# power.net
KiCad netlist of a schematic drawn in Altium Designer
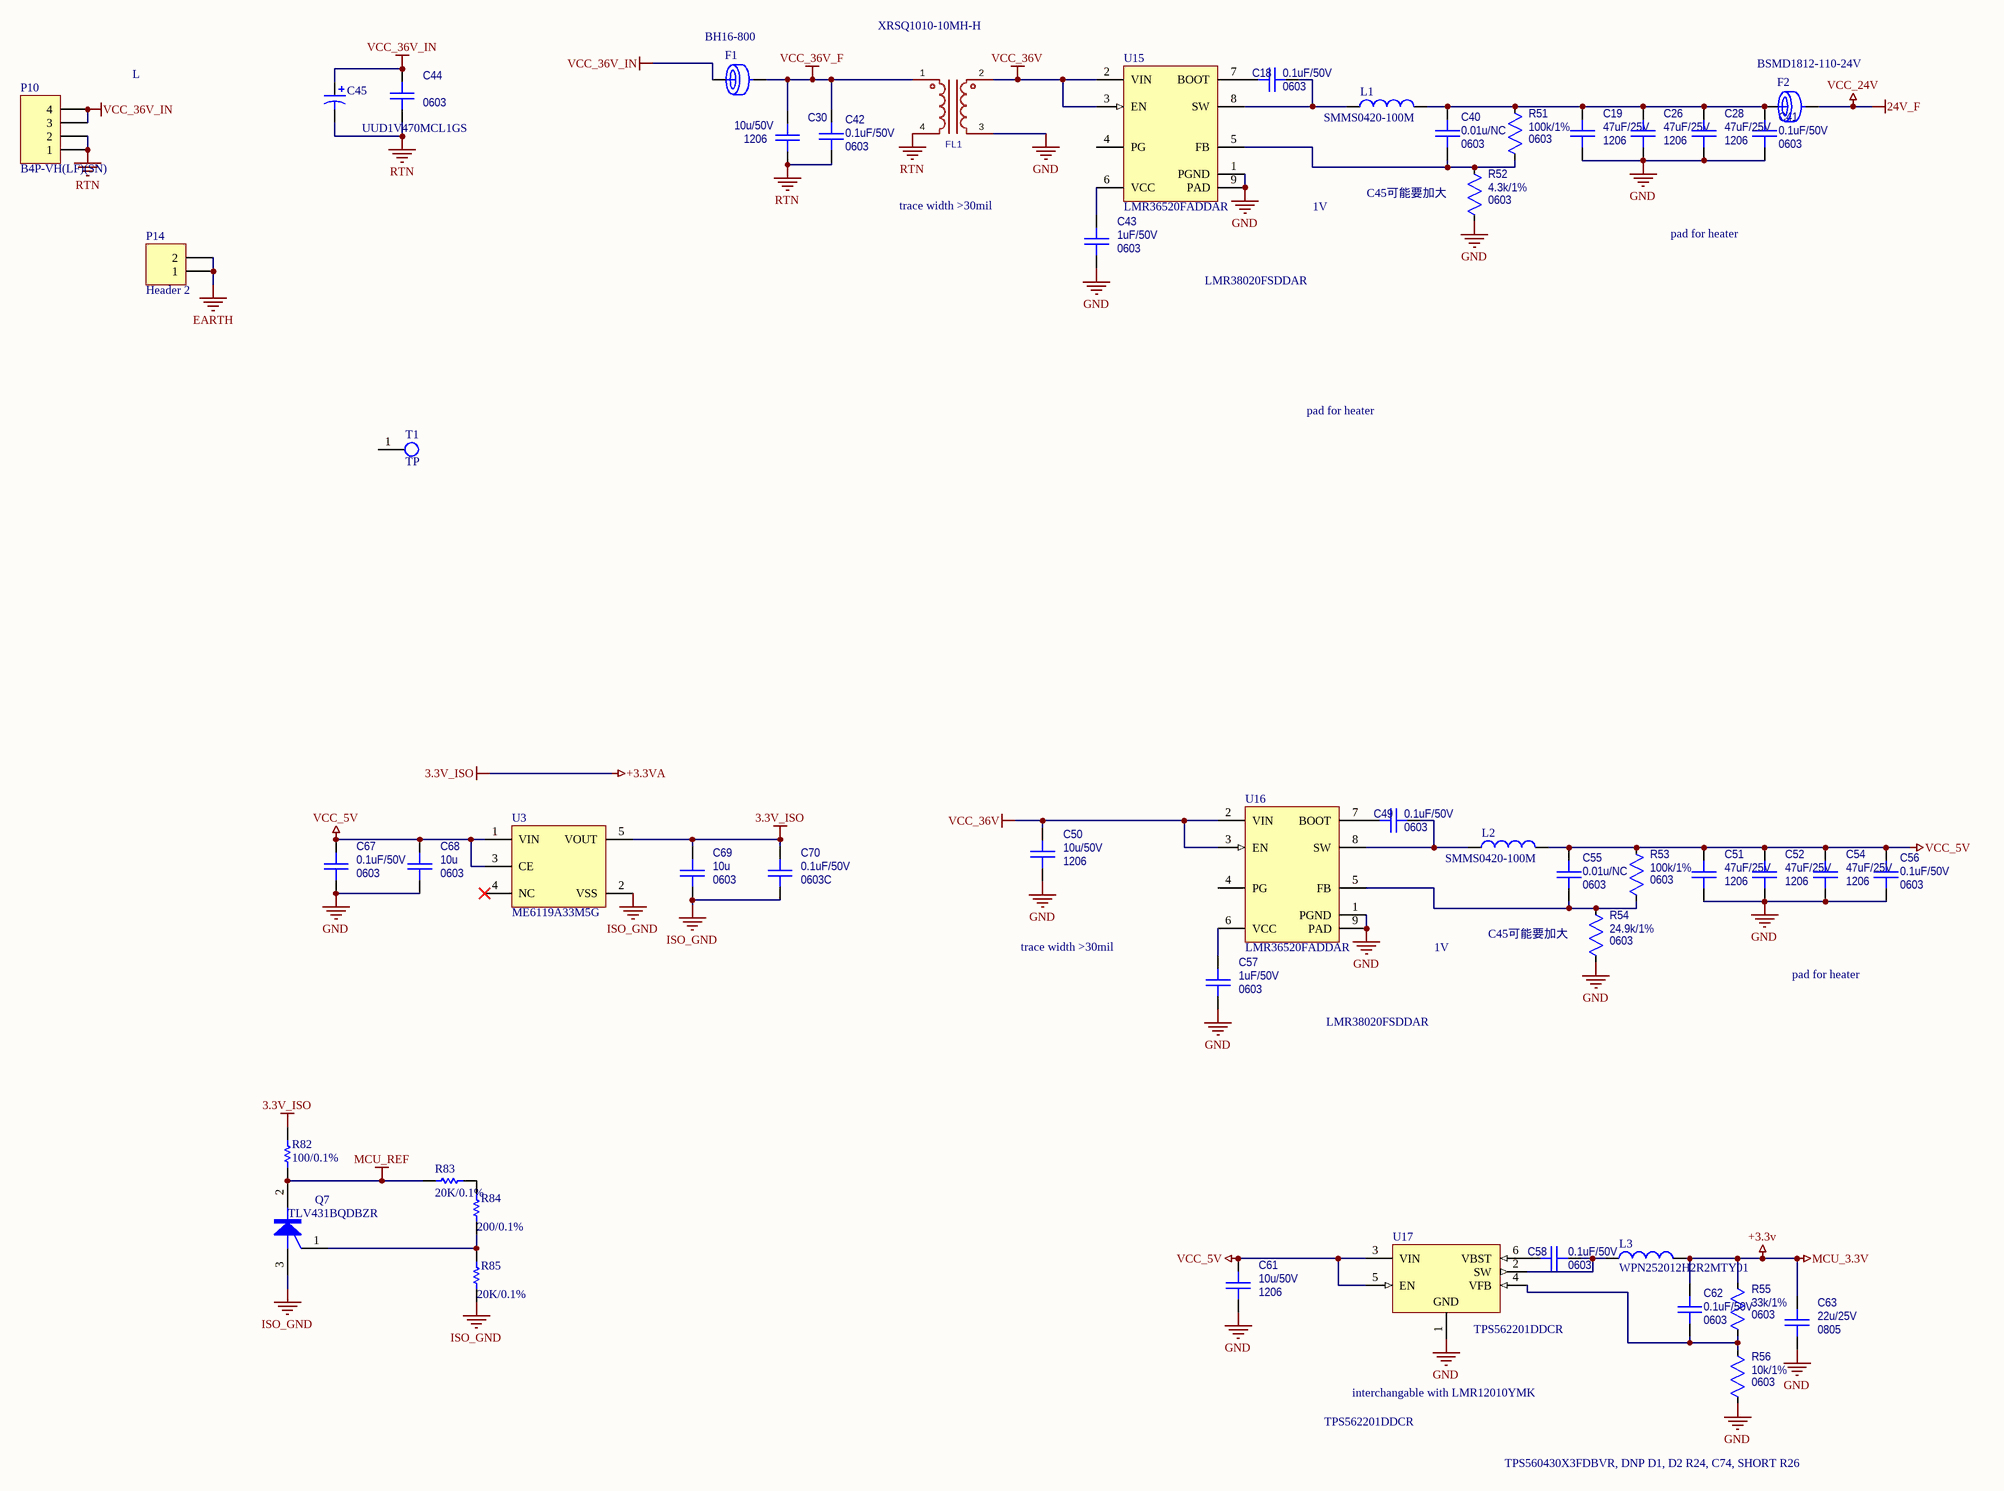
[diagram p0: power.SchDoc]

(export (version "E")
  (design (tool "Eeschema 10.0.6"))
  (components
    (comp (ref "C18")
      (value "0.1uF/50V")
      (footprint "0603C")
      (fields (field (name "PACKAGE") "0603"))
      (libsource (lib "Karl") (part "Capacitor_0603"))
    )
    (comp (ref "C19")
      (value "47uF/25V")
      (footprint "CAPC3216X156N_1206")
      (fields (field (name "PACKAGE") "1206"))
      (libsource (lib "Karl") (part "Capacitor_1206"))
    )
    (comp (ref "C26")
      (value "47uF/25V")
      (footprint "CAPC3216X156N_1206")
      (fields (field (name "PACKAGE") "1206"))
      (libsource (lib "Karl") (part "Capacitor_1206"))
    )
    (comp (ref "C28")
      (value "47uF/25V")
      (footprint "CAPC3216X156N_1206")
      (fields (field (name "PACKAGE") "1206"))
      (libsource (lib "Karl") (part "Capacitor_1206"))
    )
    (comp (ref "C30")
      (value "10u/50V")
      (footprint "CAPC3216X156N_1206")
      (fields (field (name "PACKAGE") "1206"))
      (libsource (lib "Karl") (part "Capacitor_1206"))
    )
    (comp (ref "C40")
      (value "0.01u/NC")
      (footprint "0603C")
      (fields (field (name "PACKAGE") "0603") (field (name "Comment") "0.01uF/50V"))
      (libsource (lib "Karl") (part "Capacitor_0603"))
    )
    (comp (ref "C41")
      (value "0.1uF/50V")
      (footprint "0603C")
      (fields (field (name "PACKAGE") "0603"))
      (libsource (lib "Karl") (part "Capacitor_0603"))
    )
    (comp (ref "C42")
      (value "0.1uF/50V")
      (footprint "0603C")
      (fields (field (name "PACKAGE") "0603"))
      (libsource (lib "Karl") (part "Capacitor_0603"))
    )
    (comp (ref "C43")
      (value "1uF/50V")
      (footprint "0603C")
      (fields (field (name "PACKAGE") "0603"))
      (libsource (lib "Karl") (part "Capacitor_0603"))
    )
    (comp (ref "C44")
      (value "10uF/16V")
      (footprint "0603c")
      (description "Capacitor, MLCC")
      (fields (field (name "PACKAGE") "0603"))
      (libsource (lib "Karl") (part "Capacitor_0603"))
    )
    (comp (ref "C45")
      (value "UUD1V470MCL1GS")
      (footprint "Φ10×10")
      (description "Polarized Capacitor (Radial)")
      (libsource (lib "Miscellaneous Devices") (part "Cap Pol1"))
    )
    (comp (ref "C49")
      (value "0.1uF/50V")
      (footprint "0603C")
      (fields (field (name "PACKAGE") "0603"))
      (libsource (lib "Karl") (part "Capacitor_0603"))
    )
    (comp (ref "C50")
      (value "10u/50V")
      (footprint "CAPC3216X156N_1206")
      (fields (field (name "PACKAGE") "1206"))
      (libsource (lib "Karl") (part "Capacitor_1206"))
    )
    (comp (ref "C51")
      (value "47uF/25V")
      (footprint "CAPC3216X156N_1206")
      (fields (field (name "PACKAGE") "1206"))
      (libsource (lib "Karl") (part "Capacitor_1206"))
    )
    (comp (ref "C52")
      (value "47uF/25V")
      (footprint "CAPC3216X156N_1206")
      (fields (field (name "PACKAGE") "1206"))
      (libsource (lib "Karl") (part "Capacitor_1206"))
    )
    (comp (ref "C54")
      (value "47uF/25V")
      (footprint "CAPC3216X156N_1206")
      (fields (field (name "PACKAGE") "1206"))
      (libsource (lib "Karl") (part "Capacitor_1206"))
    )
    (comp (ref "C55")
      (value "0.01u/NC")
      (footprint "0603C")
      (fields (field (name "PACKAGE") "0603") (field (name "Comment") "0.01uF/50V"))
      (libsource (lib "Karl") (part "Capacitor_0603"))
    )
    (comp (ref "C56")
      (value "0.1uF/50V")
      (footprint "0603C")
      (fields (field (name "PACKAGE") "0603"))
      (libsource (lib "Karl") (part "Capacitor_0603"))
    )
    (comp (ref "C57")
      (value "1uF/50V")
      (footprint "0603C")
      (fields (field (name "PACKAGE") "0603"))
      (libsource (lib "Karl") (part "Capacitor_0603"))
    )
    (comp (ref "C58")
      (value "0.1uF/50V")
      (footprint "0603C")
      (fields (field (name "PACKAGE") "0603"))
      (libsource (lib "Karl") (part "Capacitor_0603"))
    )
    (comp (ref "C61")
      (value "10u/50V")
      (footprint "CAPC3216X156N_1206")
      (fields (field (name "PACKAGE") "1206"))
      (libsource (lib "Karl") (part "Capacitor_0805"))
    )
    (comp (ref "C62")
      (value "0.1uF/50V")
      (footprint "0603C")
      (fields (field (name "PACKAGE") "0603"))
      (libsource (lib "Karl") (part "Capacitor_0603"))
    )
    (comp (ref "C63")
      (value "22u/25V")
      (footprint "CAPC2012X127N_0805")
      (fields (field (name "PACKAGE") "0805"))
      (libsource (lib "Karl") (part "Capacitor_0805"))
    )
    (comp (ref "C67")
      (value "0.1uF/50V")
      (footprint "0603C")
      (description "Capacitor, MLCC")
      (fields (field (name "PACKAGE") "0603"))
      (libsource (lib "Karl") (part "Capacitor_0603"))
    )
    (comp (ref "C68")
      (value "10u")
      (footprint "0603c")
      (description "Capacitor, MLCC")
      (fields (field (name "PACKAGE") "0603") (field (name "Comment") "10uF/16V"))
      (libsource (lib "Karl") (part "Capacitor_0603"))
    )
    (comp (ref "C69")
      (value "10u")
      (footprint "0603c")
      (description "Capacitor, MLCC")
      (fields (field (name "PACKAGE") "0603") (field (name "Comment") "10uF/16V"))
      (libsource (lib "Karl") (part "Capacitor_0603"))
    )
    (comp (ref "C70")
      (value "0.1uF/50V")
      (footprint "0603C")
      (description "Capacitor, MLCC")
      (fields (field (name "PACKAGE") "0603C"))
      (libsource (lib "Karl") (part "Capacitor_0402"))
    )
    (comp (ref "F1")
      (value "BH16-800")
      (footprint "FUSE-TH_L14.0-W3.0-P5.10-D0.8-LS1.20")
      (description "Ferrite Bead Chip")
      (libsource (lib "Karl") (part "FBC0603"))
    )
    (comp (ref "F2")
      (value "BSMD1812-110-24V")
      (footprint "1812-F")
      (description "Ferrite Bead Chip")
      (libsource (lib "Karl") (part "FBC0603"))
    )
    (comp (ref "FL1")
      (value "XRSQ1010-10MH-H")
      (footprint "IND-TH_4P-L14.0-W12.0_XRSQ1010-10MH-H")
      (libsource (lib "altium-import") (part "root_0_XRSQ1010-10MH-H_"))
    )
    (comp (ref "L1")
      (value "SMMS0420-100M")
      (footprint "IND-SMD_L4.5-W4.5_SMMS0420:IND-SMD_L4.5-W4.5_SMMS0420")
      (description "Metal alloy Power Inductor, 10 uH, ±20%, 1210 (3225)")
      (libsource (lib "Bogen") (part "1276AS-H-100M=P2"))
    )
    (comp (ref "L2")
      (value "SMMS0420-100M")
      (footprint "IND-SMD_L4.5-W4.5_SMMS0420:IND-SMD_L4.5-W4.5_SMMS0420")
      (description "Metal alloy Power Inductor, 10 uH, ±20%, 1210 (3225)")
      (libsource (lib "Bogen") (part "1276AS-H-100M=P2"))
    )
    (comp (ref "L3")
      (value "WPN252012H2R2MTY01")
      (footprint "PULS-BDCD00252012_V")
      (libsource (lib "Bogen") (part "BDCD002520122R2MS1"))
    )
    (comp (ref "P10")
      (value "B4P-VH(LF)(SN)")
      (footprint "CONN-TH_4P-P3.96_HX-VH3.96-4P-ZZ")
      (description "Header, 4-Pin")
      (libsource (lib "Miscellaneous Connectors") (part "Header 4"))
    )
    (comp (ref "P14")
      (value "Header 2")
      (footprint "插片端子4.8*0.8mm")
      (description "Header, 2-Pin")
      (libsource (lib "Miscellaneous Connectors") (part "Header 2"))
    )
    (comp (ref "Q7")
      (value "TLV431BQDBZR")
      (footprint "SOT23-3")
      (description "Programmable Unijunction Transistor")
      (libsource (lib "Miscellaneous Devices") (part "PUT"))
    )
    (comp (ref "R51")
      (value "100k/1%")
      (footprint "0603R")
      (fields (field (name "PACKAGE") "0603"))
      (libsource (lib "Karl") (part "Resistor_0603"))
    )
    (comp (ref "R52")
      (value "4.3k/1%")
      (footprint "0603R")
      (fields (field (name "PACKAGE") "0603"))
      (libsource (lib "Karl") (part "Resistor_0603"))
    )
    (comp (ref "R53")
      (value "100k/1%")
      (footprint "0603R")
      (fields (field (name "PACKAGE") "0603"))
      (libsource (lib "Karl") (part "Resistor_0603"))
    )
    (comp (ref "R54")
      (value "24.9k/1%")
      (footprint "0603R")
      (fields (field (name "PACKAGE") "0603"))
      (libsource (lib "Karl") (part "Resistor_0603"))
    )
    (comp (ref "R55")
      (value "33k/1%")
      (footprint "0603R")
      (fields (field (name "PACKAGE") "0603"))
      (libsource (lib "Karl") (part "Resistor_0603"))
    )
    (comp (ref "R56")
      (value "10k/1%")
      (footprint "0603R")
      (fields (field (name "PACKAGE") "0603"))
      (libsource (lib "Karl") (part "Resistor_0603"))
    )
    (comp (ref "R82")
      (value "100/0.1%")
      (footprint "0603R")
      (description "Resistor")
      (libsource (lib "Miscellaneous Devices") (part "Res1"))
    )
    (comp (ref "R83")
      (value "20K/0.1%")
      (footprint "0603R")
      (description "Resistor")
      (libsource (lib "Miscellaneous Devices") (part "Res1"))
    )
    (comp (ref "R84")
      (value "200/0.1%")
      (footprint "0603R")
      (description "Resistor")
      (libsource (lib "Miscellaneous Devices") (part "Res1"))
    )
    (comp (ref "R85")
      (value "20K/0.1%")
      (footprint "0603R")
      (description "Resistor")
      (libsource (lib "Miscellaneous Devices") (part "Res1"))
    )
    (comp (ref "T1") (value "TP") (footprint "SQP-1181C") (libsource (lib "Schlib_20110825") (part "TP")))
    (comp (ref "U3")
      (value "ME6119A33M5G")
      (footprint "MCRN-SOT23-5_V")
      (libsource (lib "Bogen") (part "ME6119C50M5G"))
    )
    (comp (ref "U15")
      (value "LMR36520FADDAR")
      (footprint "DDA0008A_M")
      (libsource (lib "Bogen") (part "LMR36520FADDAR"))
    )
    (comp (ref "U16")
      (value "LMR36520FADDAR")
      (footprint "DDA0008A_M")
      (libsource (lib "Bogen") (part "LMR36520FADDAR"))
    )
    (comp (ref "U17")
      (value "TPS562201DDCR")
      (footprint "DDC0006A_L")
      (libsource (lib "Bogen") (part "TPS562201DDCR"))
    )
  )
  (nets
    (net (code "1") (name "+3.3VA") (class "Default")
      (node (ref "C69") (pin "1") (pinfunction "1_1") (pintype "passive"))
      (node (ref "C70") (pin "1") (pinfunction "1_1") (pintype "passive"))
      (node (ref "R82") (pin "1") (pinfunction "1_1") (pintype "passive"))
      (node (ref "U3") (pin "5") (pinfunction "VOUT_5") (pintype "passive"))
    )
    (net (code "2") (name "+3.3v") (class "Default")
      (node (ref "C62") (pin "1") (pinfunction "1_1") (pintype "passive"))
      (node (ref "C63") (pin "1") (pinfunction "1_1") (pintype "passive"))
      (node (ref "L3") (pin "2") (pinfunction "2_2") (pintype "passive"))
      (node (ref "R55") (pin "2") (pinfunction "2_2") (pintype "passive"))
    )
    (net (code "3") (name "24V_F") (class "Default")
      (node (ref "F2") (pin "2") (pinfunction "2_2") (pintype "passive"))
    )
    (net (code "4") (name "EARTH") (class "Default")
      (node (ref "P14") (pin "1") (pinfunction "1_1") (pintype "passive"))
      (node (ref "P14") (pin "2") (pinfunction "2_2") (pintype "passive"))
    )
    (net (code "5") (name "GND") (class "Default")
      (node (ref "C19") (pin "2") (pinfunction "2_2") (pintype "passive"))
      (node (ref "C26") (pin "2") (pinfunction "2_2") (pintype "passive"))
      (node (ref "C28") (pin "2") (pinfunction "2_2") (pintype "passive"))
      (node (ref "C41") (pin "2") (pinfunction "2_2") (pintype "passive"))
      (node (ref "C43") (pin "2") (pinfunction "2_2") (pintype "passive"))
      (node (ref "C50") (pin "2") (pinfunction "2_2") (pintype "passive"))
      (node (ref "C51") (pin "2") (pinfunction "2_2") (pintype "passive"))
      (node (ref "C52") (pin "2") (pinfunction "2_2") (pintype "passive"))
      (node (ref "C54") (pin "2") (pinfunction "2_2") (pintype "passive"))
      (node (ref "C56") (pin "2") (pinfunction "2_2") (pintype "passive"))
      (node (ref "C57") (pin "2") (pinfunction "2_2") (pintype "passive"))
      (node (ref "C61") (pin "2") (pinfunction "2_2") (pintype "passive"))
      (node (ref "C63") (pin "2") (pinfunction "2_2") (pintype "passive"))
      (node (ref "C67") (pin "2") (pinfunction "2_2") (pintype "passive"))
      (node (ref "C68") (pin "2") (pinfunction "2_2") (pintype "passive"))
      (node (ref "FL1") (pin "3") (pinfunction "3_3") (pintype "passive"))
      (node (ref "R52") (pin "1") (pinfunction "1_1") (pintype "passive"))
      (node (ref "R54") (pin "1") (pinfunction "1_1") (pintype "passive"))
      (node (ref "R56") (pin "1") (pinfunction "1_1") (pintype "passive"))
      (node (ref "U15") (pin "1") (pinfunction "PGND_1") (pintype "passive"))
      (node (ref "U15") (pin "9") (pinfunction "PAD_9") (pintype "passive"))
      (node (ref "U16") (pin "1") (pinfunction "PGND_1") (pintype "passive"))
      (node (ref "U16") (pin "9") (pinfunction "PAD_9") (pintype "passive"))
      (node (ref "U17") (pin "1") (pinfunction "GND_1") (pintype "power_in"))
    )
    (net (code "6") (name "ISO_GND") (class "Default")
      (node (ref "C69") (pin "2") (pinfunction "2_2") (pintype "passive"))
      (node (ref "C70") (pin "2") (pinfunction "2_2") (pintype "passive"))
      (node (ref "Q7") (pin "3") (pinfunction "A_3") (pintype "passive"))
      (node (ref "R85") (pin "2") (pinfunction "2_2") (pintype "passive"))
      (node (ref "U3") (pin "2") (pinfunction "VSS_2") (pintype "passive"))
    )
    (net (code "7") (name "MCU_REF") (class "Default")
      (node (ref "Q7") (pin "2") (pinfunction "K_2") (pintype "passive"))
      (node (ref "R82") (pin "2") (pinfunction "2_2") (pintype "passive"))
      (node (ref "R83") (pin "1") (pinfunction "1_1") (pintype "passive"))
    )
    (net (code "8") (name "Net-(C19-Pad1)") (class "Default")
      (node (ref "C19") (pin "1") (pinfunction "1_1") (pintype "passive"))
      (node (ref "C26") (pin "1") (pinfunction "1_1") (pintype "passive"))
      (node (ref "C28") (pin "1") (pinfunction "1_1") (pintype "passive"))
      (node (ref "C40") (pin "1") (pinfunction "1_1") (pintype "passive"))
      (node (ref "C41") (pin "1") (pinfunction "1_1") (pintype "passive"))
      (node (ref "F2") (pin "1") (pinfunction "1_1") (pintype "passive"))
      (node (ref "L1") (pin "2") (pinfunction "2_2") (pintype "passive"))
      (node (ref "R51") (pin "2") (pinfunction "2_2") (pintype "passive"))
    )
    (net (code "9") (name "Net-(Q7-G)") (class "Default")
      (node (ref "Q7") (pin "1") (pinfunction "G_1") (pintype "passive"))
      (node (ref "R84") (pin "2") (pinfunction "2_2") (pintype "passive"))
      (node (ref "R85") (pin "1") (pinfunction "1_1") (pintype "passive"))
    )
    (net (code "10") (name "Net-(R83-Pad2)") (class "Default")
      (node (ref "R83") (pin "2") (pinfunction "2_2") (pintype "passive"))
      (node (ref "R84") (pin "1") (pinfunction "1_1") (pintype "passive"))
    )
    (net (code "11") (name "Net-(U15-BOOT)") (class "Default")
      (node (ref "C18") (pin "1") (pinfunction "1_1") (pintype "passive"))
      (node (ref "U15") (pin "7") (pinfunction "BOOT_7") (pintype "passive"))
    )
    (net (code "12") (name "Net-(U15-FB)") (class "Default")
      (node (ref "C40") (pin "2") (pinfunction "2_2") (pintype "passive"))
      (node (ref "R51") (pin "1") (pinfunction "1_1") (pintype "passive"))
      (node (ref "R52") (pin "2") (pinfunction "2_2") (pintype "passive"))
      (node (ref "U15") (pin "5") (pinfunction "FB_5") (pintype "passive"))
    )
    (net (code "13") (name "Net-(U15-SW)") (class "Default")
      (node (ref "C18") (pin "2") (pinfunction "2_2") (pintype "passive"))
      (node (ref "L1") (pin "1") (pinfunction "1_1") (pintype "passive"))
      (node (ref "U15") (pin "8") (pinfunction "SW_8") (pintype "passive"))
    )
    (net (code "14") (name "Net-(U15-VCC)") (class "Default")
      (node (ref "C43") (pin "1") (pinfunction "1_1") (pintype "passive"))
      (node (ref "U15") (pin "6") (pinfunction "VCC_6") (pintype "passive"))
    )
    (net (code "15") (name "Net-(U16-BOOT)") (class "Default")
      (node (ref "C49") (pin "1") (pinfunction "1_1") (pintype "passive"))
      (node (ref "U16") (pin "7") (pinfunction "BOOT_7") (pintype "passive"))
    )
    (net (code "16") (name "Net-(U16-FB)") (class "Default")
      (node (ref "C55") (pin "2") (pinfunction "2_2") (pintype "passive"))
      (node (ref "R53") (pin "1") (pinfunction "1_1") (pintype "passive"))
      (node (ref "R54") (pin "2") (pinfunction "2_2") (pintype "passive"))
      (node (ref "U16") (pin "5") (pinfunction "FB_5") (pintype "passive"))
    )
    (net (code "17") (name "Net-(U16-SW)") (class "Default")
      (node (ref "C49") (pin "2") (pinfunction "2_2") (pintype "passive"))
      (node (ref "L2") (pin "1") (pinfunction "1_1") (pintype "passive"))
      (node (ref "U16") (pin "8") (pinfunction "SW_8") (pintype "passive"))
    )
    (net (code "18") (name "Net-(U16-VCC)") (class "Default")
      (node (ref "C57") (pin "1") (pinfunction "1_1") (pintype "passive"))
      (node (ref "U16") (pin "6") (pinfunction "VCC_6") (pintype "passive"))
    )
    (net (code "19") (name "Net-(U17-SW)") (class "Default")
      (node (ref "C58") (pin "2") (pinfunction "2_2") (pintype "passive"))
      (node (ref "L3") (pin "1") (pinfunction "1_1") (pintype "passive"))
      (node (ref "U17") (pin "2") (pinfunction "SW_2") (pintype "output"))
    )
    (net (code "20") (name "Net-(U17-VBST)") (class "Default")
      (node (ref "C58") (pin "1") (pinfunction "1_1") (pintype "passive"))
      (node (ref "U17") (pin "6") (pinfunction "VBST_6") (pintype "input"))
    )
    (net (code "21") (name "Net-(U17-VFB)") (class "Default")
      (node (ref "C62") (pin "2") (pinfunction "2_2") (pintype "passive"))
      (node (ref "R55") (pin "1") (pinfunction "1_1") (pintype "passive"))
      (node (ref "R56") (pin "2") (pinfunction "2_2") (pintype "passive"))
      (node (ref "U17") (pin "4") (pinfunction "VFB_4") (pintype "input"))
    )
    (net (code "22") (name "RTN") (class "Default")
      (node (ref "C30") (pin "2") (pinfunction "2_2") (pintype "passive"))
      (node (ref "C42") (pin "2") (pinfunction "2_2") (pintype "passive"))
      (node (ref "C44") (pin "2") (pinfunction "2_2") (pintype "passive"))
      (node (ref "C45") (pin "2") (pinfunction "2_2") (pintype "passive"))
      (node (ref "FL1") (pin "4") (pinfunction "4_4") (pintype "passive"))
      (node (ref "P10") (pin "1") (pinfunction "1_1") (pintype "passive"))
      (node (ref "P10") (pin "2") (pinfunction "2_2") (pintype "passive"))
    )
    (net (code "23") (name "VCC_5V") (class "Default")
      (node (ref "C51") (pin "1") (pinfunction "1_1") (pintype "passive"))
      (node (ref "C52") (pin "1") (pinfunction "1_1") (pintype "passive"))
      (node (ref "C54") (pin "1") (pinfunction "1_1") (pintype "passive"))
      (node (ref "C55") (pin "1") (pinfunction "1_1") (pintype "passive"))
      (node (ref "C56") (pin "1") (pinfunction "1_1") (pintype "passive"))
      (node (ref "C61") (pin "1") (pinfunction "1_1") (pintype "passive"))
      (node (ref "C67") (pin "1") (pinfunction "1_1") (pintype "passive"))
      (node (ref "C68") (pin "1") (pinfunction "1_1") (pintype "passive"))
      (node (ref "L2") (pin "2") (pinfunction "2_2") (pintype "passive"))
      (node (ref "R53") (pin "2") (pinfunction "2_2") (pintype "passive"))
      (node (ref "U17") (pin "3") (pinfunction "VIN_3") (pintype "power_in"))
      (node (ref "U17") (pin "5") (pinfunction "EN_5") (pintype "input"))
      (node (ref "U3") (pin "1") (pinfunction "VIN_1") (pintype "passive"))
      (node (ref "U3") (pin "3") (pinfunction "CE_3") (pintype "passive"))
    )
    (net (code "24") (name "VCC_36V") (class "Default")
      (node (ref "C50") (pin "1") (pinfunction "1_1") (pintype "passive"))
      (node (ref "FL1") (pin "2") (pinfunction "2_2") (pintype "passive"))
      (node (ref "U15") (pin "2") (pinfunction "VIN_2") (pintype "passive"))
      (node (ref "U15") (pin "3") (pinfunction "EN_3") (pintype "input"))
      (node (ref "U16") (pin "2") (pinfunction "VIN_2") (pintype "passive"))
      (node (ref "U16") (pin "3") (pinfunction "EN_3") (pintype "input"))
    )
    (net (code "25") (name "VCC_36V_F") (class "Default")
      (node (ref "C30") (pin "1") (pinfunction "1_1") (pintype "passive"))
      (node (ref "C42") (pin "1") (pinfunction "1_1") (pintype "passive"))
      (node (ref "F1") (pin "2") (pinfunction "2_2") (pintype "passive"))
      (node (ref "FL1") (pin "1") (pinfunction "1_1") (pintype "passive"))
    )
    (net (code "26") (name "VCC_36V_IN") (class "Default")
      (node (ref "C44") (pin "1") (pinfunction "1_1") (pintype "passive"))
      (node (ref "C45") (pin "1") (pinfunction "1_1") (pintype "passive"))
      (node (ref "F1") (pin "1") (pinfunction "1_1") (pintype "passive"))
      (node (ref "P10") (pin "3") (pinfunction "3_3") (pintype "passive"))
      (node (ref "P10") (pin "4") (pinfunction "4_4") (pintype "passive"))
    )
    (net (code "27") (name "unconnected-(T1-Pad1)") (class "Default")
      (node (ref "T1") (pin "1") (pintype "passive"))
    )
    (net (code "28") (name "unconnected-(U3-NC-Pad4)") (class "Default")
      (node (ref "U3") (pin "4") (pinfunction "NC_4") (pintype "passive+no_connect"))
    )
    (net (code "29") (name "unconnected-(U15-PG-Pad4)") (class "Default")
      (node (ref "U15") (pin "4") (pinfunction "PG_4") (pintype "passive"))
    )
    (net (code "30") (name "unconnected-(U16-PG-Pad4)") (class "Default")
      (node (ref "U16") (pin "4") (pinfunction "PG_4") (pintype "passive"))
    )
  )
)
